# SulaMatikV2.net
KiCad netlist of a schematic drawn in EAGLE
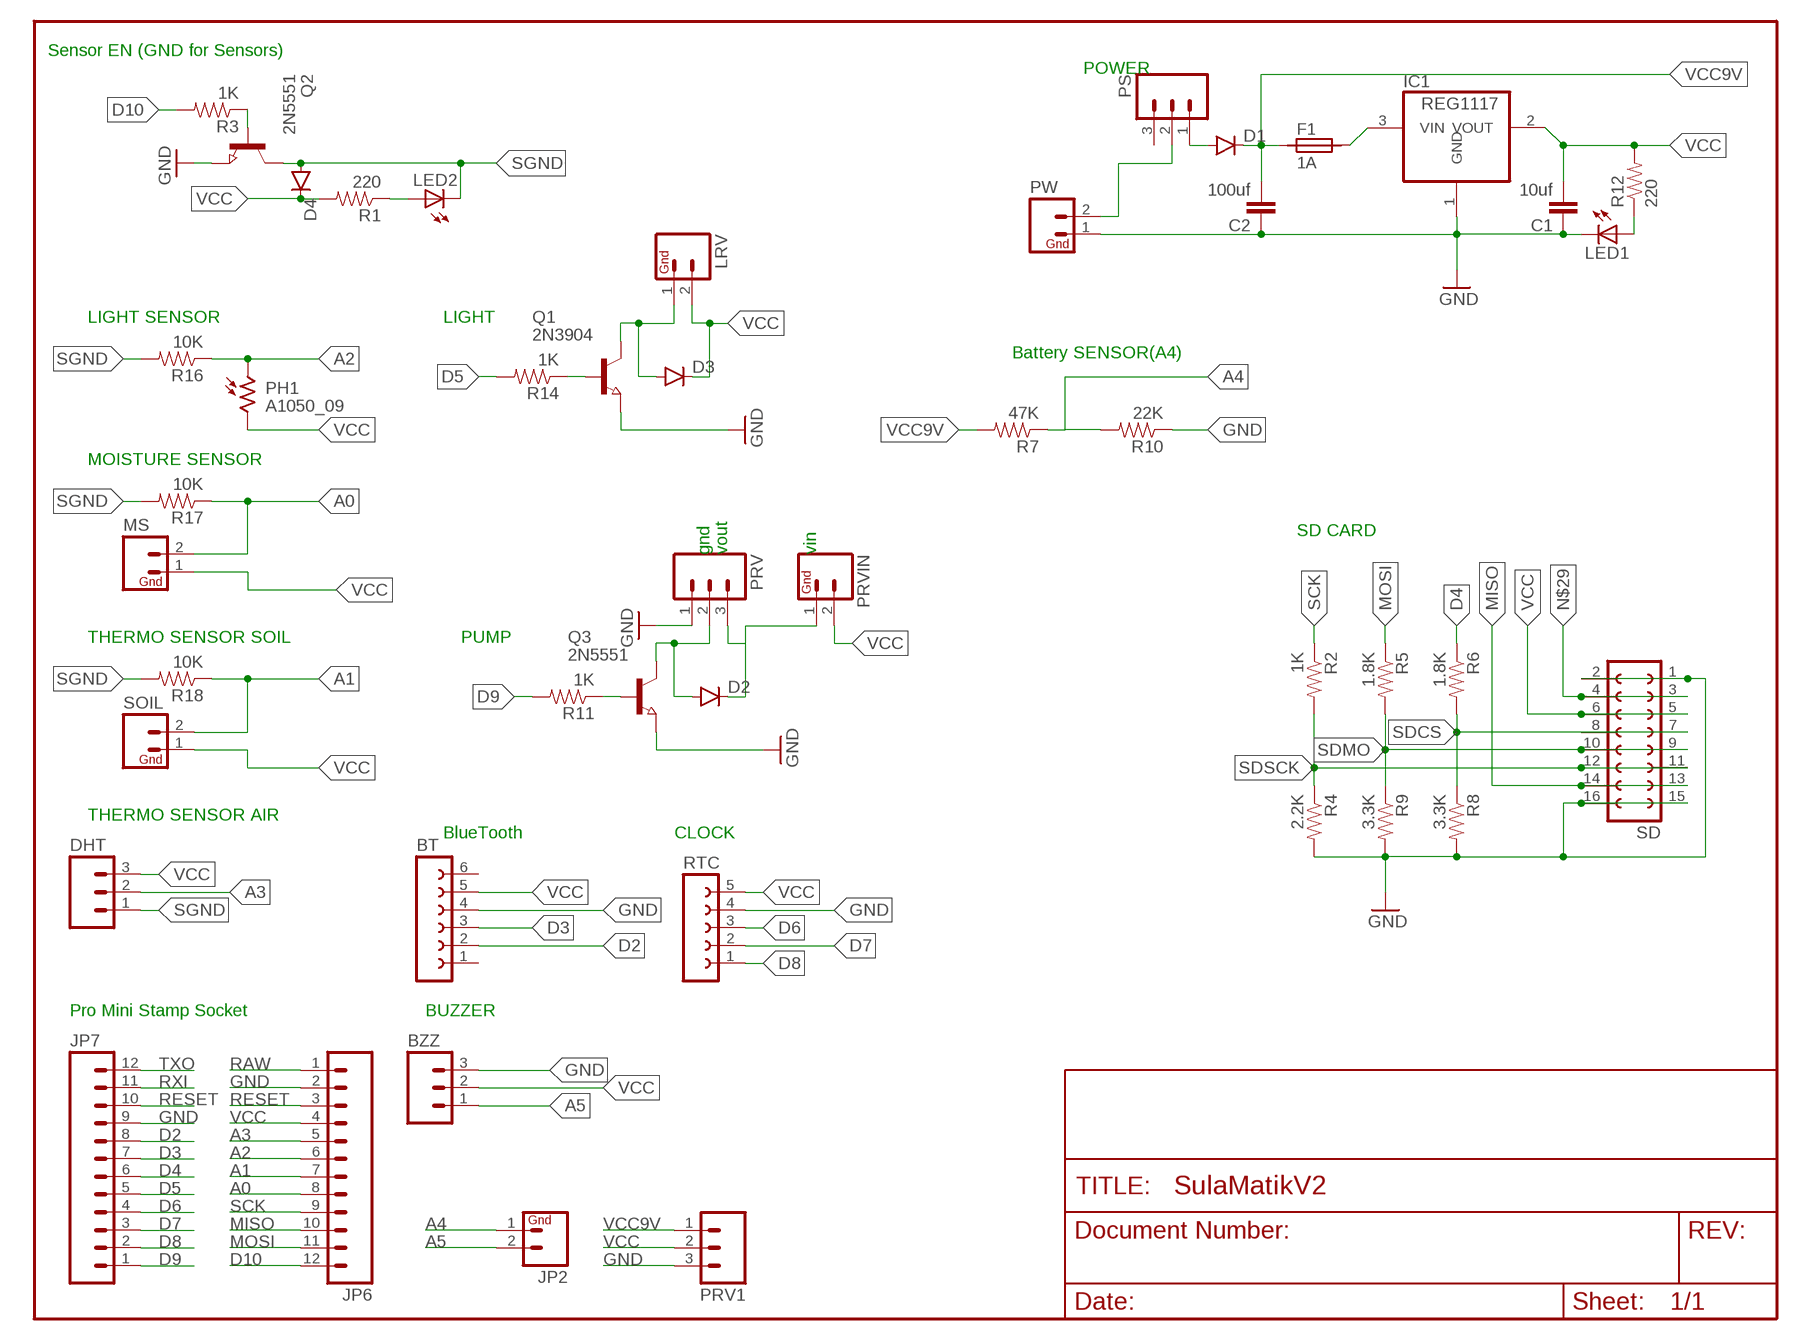
[diagram p0: schematic, sheet 1]

(export (version "E")
  (design (tool "Eeschema 10.0.6"))
  (components
    (comp (ref "BT")
      (value "FE06-1")
      (footprint "eagle-import:FE06")
      (libsource (lib "eagle-import") (part "FE06-1"))
    )
    (comp (ref "BZZ")
      (value "M03PTH")
      (footprint "eagle-import:1X03")
      (libsource (lib "eagle-import") (part "M03PTH"))
    )
    (comp (ref "C1")
      (value "10uf")
      (footprint "eagle-import:0805")
      (libsource (lib "eagle-import") (part "CAP0805"))
    )
    (comp (ref "C2")
      (value "100uf")
      (footprint "eagle-import:0805")
      (libsource (lib "eagle-import") (part "CAP0805"))
    )
    (comp (ref "D1")
      (value "DIODESMA")
      (footprint "eagle-import:SMA-DIODE")
      (libsource (lib "eagle-import") (part "DIODESMA"))
    )
    (comp (ref "D2")
      (value "DIODESMA")
      (footprint "eagle-import:SMA-DIODE")
      (libsource (lib "eagle-import") (part "DIODESMA"))
    )
    (comp (ref "D3")
      (value "DIODESMA")
      (footprint "eagle-import:SMA-DIODE")
      (libsource (lib "eagle-import") (part "DIODESMA"))
    )
    (comp (ref "D4")
      (value "DIODESMA")
      (footprint "eagle-import:SMA-DIODE")
      (libsource (lib "eagle-import") (part "DIODESMA"))
    )
    (comp (ref "DHT")
      (value "M03PTH")
      (footprint "eagle-import:1X03")
      (libsource (lib "eagle-import") (part "M03PTH"))
    )
    (comp (ref "F1")
      (value "1A")
      (footprint "eagle-import:1820")
      (libsource (lib "eagle-import") (part "SIBA194600"))
    )
    (comp (ref "IC1")
      (value "REG1117")
      (footprint "eagle-import:SOT223")
      (libsource (lib "eagle-import") (part "REG1117"))
    )
    (comp (ref "JP2")
      (value "M02PTH")
      (footprint "eagle-import:1X02")
      (libsource (lib "eagle-import") (part "M02PTH"))
    )
    (comp (ref "JP6")
      (value "M12PTH")
      (footprint "eagle-import:1X12")
      (libsource (lib "eagle-import") (part "M12PTH"))
    )
    (comp (ref "JP7")
      (value "M12PTH")
      (footprint "eagle-import:1X12")
      (libsource (lib "eagle-import") (part "M12PTH"))
    )
    (comp (ref "LED1")
      (value "LEDCHIP-LED0805")
      (footprint "eagle-import:CHIP-LED0805")
      (libsource (lib "eagle-import") (part "LEDCHIP-LED0805"))
    )
    (comp (ref "LED2")
      (value "LEDCHIP-LED0805")
      (footprint "eagle-import:CHIP-LED0805")
      (libsource (lib "eagle-import") (part "LEDCHIP-LED0805"))
    )
    (comp (ref "LRV")
      (value "M02PTH")
      (footprint "eagle-import:1X02")
      (libsource (lib "eagle-import") (part "M02PTH"))
    )
    (comp (ref "MS")
      (value "M02PTH")
      (footprint "eagle-import:1X02")
      (libsource (lib "eagle-import") (part "M02PTH"))
    )
    (comp (ref "PH1")
      (value "A1050_09")
      (footprint "eagle-import:T0-46-A10XX")
      (libsource (lib "eagle-import") (part "A1050_09"))
    )
    (comp (ref "PRV")
      (value "M03PTH")
      (footprint "eagle-import:1X03")
      (libsource (lib "eagle-import") (part "M03PTH"))
    )
    (comp (ref "PRV1")
      (value "M03PTH")
      (footprint "eagle-import:1X03")
      (libsource (lib "eagle-import") (part "M03PTH"))
    )
    (comp (ref "PRVIN")
      (value "M02PTH")
      (footprint "eagle-import:1X02")
      (libsource (lib "eagle-import") (part "M02PTH"))
    )
    (comp (ref "PS")
      (value "M03PTH")
      (footprint "eagle-import:1X03")
      (libsource (lib "eagle-import") (part "M03PTH"))
    )
    (comp (ref "PW")
      (value "M02PTH")
      (footprint "eagle-import:1X02")
      (libsource (lib "eagle-import") (part "M02PTH"))
    )
    (comp (ref "Q1")
      (value "2N3904")
      (footprint "eagle-import:SOT23")
      (libsource (lib "eagle-import") (part "NPN-TRANSISTOR_SOT23"))
    )
    (comp (ref "Q2")
      (value "2N5551")
      (footprint "eagle-import:SOT23")
      (libsource (lib "eagle-import") (part "NPN-TRANSISTOR_SOT23"))
    )
    (comp (ref "Q3")
      (value "2N5551")
      (footprint "eagle-import:SOT23")
      (libsource (lib "eagle-import") (part "NPN-TRANSISTOR_SOT23"))
    )
    (comp (ref "R1")
      (value "220")
      (footprint "eagle-import:0805")
      (libsource (lib "eagle-import") (part "RESISTOR0805-RES"))
    )
    (comp (ref "R2")
      (value "1K")
      (footprint "eagle-import:0805")
      (libsource (lib "eagle-import") (part "RESISTOR0805-RES"))
    )
    (comp (ref "R3")
      (value "1K")
      (footprint "eagle-import:0805")
      (libsource (lib "eagle-import") (part "RESISTOR0805-RES"))
    )
    (comp (ref "R4")
      (value "2.2K")
      (footprint "eagle-import:0805")
      (libsource (lib "eagle-import") (part "RESISTOR0805-RES"))
    )
    (comp (ref "R5")
      (value "1.8K")
      (footprint "eagle-import:0805")
      (libsource (lib "eagle-import") (part "RESISTOR0805-RES"))
    )
    (comp (ref "R6")
      (value "1.8K")
      (footprint "eagle-import:0805")
      (libsource (lib "eagle-import") (part "RESISTOR0805-RES"))
    )
    (comp (ref "R7")
      (value "47K")
      (footprint "eagle-import:0805")
      (libsource (lib "eagle-import") (part "RESISTOR0805-RES"))
    )
    (comp (ref "R8")
      (value "3.3K")
      (footprint "eagle-import:0805")
      (libsource (lib "eagle-import") (part "RESISTOR0805-RES"))
    )
    (comp (ref "R9")
      (value "3.3K")
      (footprint "eagle-import:0805")
      (libsource (lib "eagle-import") (part "RESISTOR0805-RES"))
    )
    (comp (ref "R10")
      (value "22K")
      (footprint "eagle-import:0805")
      (libsource (lib "eagle-import") (part "RESISTOR0805-RES"))
    )
    (comp (ref "R11")
      (value "1K")
      (footprint "eagle-import:0805")
      (libsource (lib "eagle-import") (part "RESISTOR0805-RES"))
    )
    (comp (ref "R12")
      (value "220")
      (footprint "eagle-import:0805")
      (libsource (lib "eagle-import") (part "RESISTOR0805-RES"))
    )
    (comp (ref "R14")
      (value "1K")
      (footprint "eagle-import:0805")
      (libsource (lib "eagle-import") (part "RESISTOR0805-RES"))
    )
    (comp (ref "R16")
      (value "10K")
      (footprint "eagle-import:0805")
      (libsource (lib "eagle-import") (part "RESISTOR0805-RES"))
    )
    (comp (ref "R17")
      (value "10K")
      (footprint "eagle-import:0805")
      (libsource (lib "eagle-import") (part "RESISTOR0805-RES"))
    )
    (comp (ref "R18")
      (value "10K")
      (footprint "eagle-import:0805")
      (libsource (lib "eagle-import") (part "RESISTOR0805-RES"))
    )
    (comp (ref "RTC")
      (value "FE05-1")
      (footprint "eagle-import:FE05-1")
      (libsource (lib "eagle-import") (part "FE05-1"))
    )
    (comp (ref "SD")
      (value "FE08-2")
      (footprint "eagle-import:FE08-2")
      (libsource (lib "eagle-import") (part "FE08-2"))
    )
    (comp (ref "SOIL")
      (value "M02PTH")
      (footprint "eagle-import:1X02")
      (libsource (lib "eagle-import") (part "M02PTH"))
    )
  )
  (nets
    (net (code "1") (name "/RAW") (class "Default")
      (node (ref "JP6") (pin "1") (pinfunction "1_1") (pintype "passive"))
    )
    (net (code "2") (name "/RESET") (class "Default")
      (node (ref "JP6") (pin "3") (pinfunction "3_3") (pintype "passive"))
      (node (ref "JP7") (pin "10") (pinfunction "10_10") (pintype "passive"))
    )
    (net (code "3") (name "/RXI") (class "Default")
      (node (ref "JP7") (pin "11") (pinfunction "11_11") (pintype "passive"))
    )
    (net (code "4") (name "/TXO") (class "Default")
      (node (ref "JP7") (pin "12") (pinfunction "12_12") (pintype "passive"))
    )
    (net (code "5") (name "A0") (class "Default")
      (node (ref "JP6") (pin "8") (pinfunction "8_8") (pintype "passive"))
      (node (ref "MS") (pin "2") (pinfunction "2_2") (pintype "passive"))
      (node (ref "R17") (pin "1") (pinfunction "1_1") (pintype "passive"))
    )
    (net (code "6") (name "A1") (class "Default")
      (node (ref "JP6") (pin "7") (pinfunction "7_7") (pintype "passive"))
      (node (ref "R18") (pin "1") (pinfunction "1_1") (pintype "passive"))
      (node (ref "SOIL") (pin "2") (pinfunction "2_2") (pintype "passive"))
    )
    (net (code "7") (name "A2") (class "Default")
      (node (ref "JP6") (pin "6") (pinfunction "6_6") (pintype "passive"))
      (node (ref "PH1") (pin "1") (pinfunction "1_1") (pintype "passive"))
      (node (ref "R16") (pin "1") (pinfunction "1_1") (pintype "passive"))
    )
    (net (code "8") (name "A3") (class "Default")
      (node (ref "DHT") (pin "2") (pinfunction "2_2") (pintype "passive"))
      (node (ref "JP6") (pin "5") (pinfunction "5_5") (pintype "passive"))
    )
    (net (code "9") (name "A4") (class "Default")
      (node (ref "JP2") (pin "1") (pinfunction "1_1") (pintype "passive"))
      (node (ref "R10") (pin "2") (pinfunction "2_2") (pintype "passive"))
      (node (ref "R7") (pin "1") (pinfunction "1_1") (pintype "passive"))
    )
    (net (code "10") (name "A5") (class "Default")
      (node (ref "BZZ") (pin "1") (pinfunction "1_1") (pintype "passive"))
      (node (ref "JP2") (pin "2") (pinfunction "2_2") (pintype "passive"))
    )
    (net (code "11") (name "D2") (class "Default")
      (node (ref "BT") (pin "2") (pinfunction "2_2") (pintype "passive"))
      (node (ref "JP7") (pin "8") (pinfunction "8_8") (pintype "passive"))
    )
    (net (code "12") (name "D3") (class "Default")
      (node (ref "BT") (pin "3") (pinfunction "3_3") (pintype "passive"))
      (node (ref "JP7") (pin "7") (pinfunction "7_7") (pintype "passive"))
    )
    (net (code "13") (name "D4") (class "Default")
      (node (ref "JP7") (pin "6") (pinfunction "6_6") (pintype "passive"))
      (node (ref "R6") (pin "1") (pinfunction "1_1") (pintype "passive"))
    )
    (net (code "14") (name "D5") (class "Default")
      (node (ref "JP7") (pin "5") (pinfunction "5_5") (pintype "passive"))
      (node (ref "R14") (pin "2") (pinfunction "2_2") (pintype "passive"))
    )
    (net (code "15") (name "D6") (class "Default")
      (node (ref "JP7") (pin "4") (pinfunction "4_4") (pintype "passive"))
      (node (ref "RTC") (pin "3") (pinfunction "3_3") (pintype "passive"))
    )
    (net (code "16") (name "D7") (class "Default")
      (node (ref "JP7") (pin "3") (pinfunction "3_3") (pintype "passive"))
      (node (ref "RTC") (pin "2") (pinfunction "2_2") (pintype "passive"))
    )
    (net (code "17") (name "D8") (class "Default")
      (node (ref "JP7") (pin "2") (pinfunction "2_2") (pintype "passive"))
      (node (ref "RTC") (pin "1") (pinfunction "1_1") (pintype "passive"))
    )
    (net (code "18") (name "D9") (class "Default")
      (node (ref "JP7") (pin "1") (pinfunction "1_1") (pintype "passive"))
      (node (ref "R11") (pin "2") (pinfunction "2_2") (pintype "passive"))
    )
    (net (code "19") (name "D10") (class "Default")
      (node (ref "JP6") (pin "12") (pinfunction "12_12") (pintype "passive"))
      (node (ref "R3") (pin "2") (pinfunction "2_2") (pintype "passive"))
    )
    (net (code "20") (name "GND") (class "Default")
      (node (ref "BT") (pin "4") (pinfunction "4_4") (pintype "passive"))
      (node (ref "BZZ") (pin "3") (pinfunction "3_3") (pintype "passive"))
      (node (ref "C1") (pin "1") (pinfunction "1_1") (pintype "passive"))
      (node (ref "C2") (pin "1") (pinfunction "1_1") (pintype "passive"))
      (node (ref "IC1") (pin "1") (pinfunction "GND_1") (pintype "power_in"))
      (node (ref "JP6") (pin "2") (pinfunction "2_2") (pintype "passive"))
      (node (ref "JP7") (pin "9") (pinfunction "9_9") (pintype "passive"))
      (node (ref "LED1") (pin "C") (pinfunction "C_C") (pintype "passive"))
      (node (ref "PRV") (pin "1") (pinfunction "1_1") (pintype "passive"))
      (node (ref "PRV1") (pin "3") (pinfunction "3_3") (pintype "passive"))
      (node (ref "PW") (pin "1") (pinfunction "1_1") (pintype "passive"))
      (node (ref "Q1") (pin "2") (pinfunction "E_2") (pintype "passive"))
      (node (ref "Q2") (pin "2") (pinfunction "E_2") (pintype "passive"))
      (node (ref "Q3") (pin "2") (pinfunction "E_2") (pintype "passive"))
      (node (ref "R10") (pin "1") (pinfunction "1_1") (pintype "passive"))
      (node (ref "R4") (pin "2") (pinfunction "2_2") (pintype "passive"))
      (node (ref "R8") (pin "2") (pinfunction "2_2") (pintype "passive"))
      (node (ref "R9") (pin "2") (pinfunction "2_2") (pintype "passive"))
      (node (ref "RTC") (pin "4") (pinfunction "4_4") (pintype "passive"))
      (node (ref "SD") (pin "1") (pinfunction "1_1") (pintype "passive"))
      (node (ref "SD") (pin "15") (pinfunction "15_15") (pintype "passive"))
      (node (ref "SD") (pin "16") (pinfunction "16_16") (pintype "passive"))
      (node (ref "SD") (pin "2") (pinfunction "2_2") (pintype "passive"))
    )
    (net (code "21") (name "MISO") (class "Default")
      (node (ref "JP6") (pin "10") (pinfunction "10_10") (pintype "passive"))
      (node (ref "SD") (pin "13") (pinfunction "13_13") (pintype "passive"))
      (node (ref "SD") (pin "14") (pinfunction "14_14") (pintype "passive"))
    )
    (net (code "22") (name "MOSI") (class "Default")
      (node (ref "JP6") (pin "11") (pinfunction "11_11") (pintype "passive"))
      (node (ref "R5") (pin "1") (pinfunction "1_1") (pintype "passive"))
    )
    (net (code "23") (name "N$29") (class "Default")
      (node (ref "SD") (pin "3") (pinfunction "3_3") (pintype "passive"))
      (node (ref "SD") (pin "4") (pinfunction "4_4") (pintype "passive"))
    )
    (net (code "24") (name "Net-(D1-PadA)") (class "Default")
      (node (ref "D1") (pin "A") (pinfunction "A_A") (pintype "passive"))
      (node (ref "PS") (pin "1") (pinfunction "1_1") (pintype "passive"))
    )
    (net (code "25") (name "Net-(D2-PadC)") (class "Default")
      (node (ref "D2") (pin "C") (pinfunction "C_C") (pintype "passive"))
      (node (ref "PRV") (pin "3") (pinfunction "3_3") (pintype "passive"))
      (node (ref "PRVIN") (pin "1") (pinfunction "1_1") (pintype "passive"))
    )
    (net (code "26") (name "Net-(IC1-VIN)") (class "Default")
      (node (ref "F1") (pin "2") (pinfunction "2_2") (pintype "passive"))
      (node (ref "IC1") (pin "3") (pinfunction "VIN_3") (pintype "input"))
    )
    (net (code "27") (name "Net-(LED1-PadA)") (class "Default")
      (node (ref "LED1") (pin "A") (pinfunction "A_A") (pintype "passive"))
      (node (ref "R12") (pin "1") (pinfunction "1_1") (pintype "passive"))
    )
    (net (code "28") (name "Net-(LED2-PadA)") (class "Default")
      (node (ref "LED2") (pin "A") (pinfunction "A_A") (pintype "passive"))
      (node (ref "R1") (pin "1") (pinfunction "1_1") (pintype "passive"))
    )
    (net (code "29") (name "Net-(PS-Pad2)") (class "Default")
      (node (ref "PS") (pin "2") (pinfunction "2_2") (pintype "passive"))
      (node (ref "PW") (pin "2") (pinfunction "2_2") (pintype "passive"))
    )
    (net (code "30") (name "Net-(Q1-B)") (class "Default")
      (node (ref "Q1") (pin "1") (pinfunction "B_1") (pintype "passive"))
      (node (ref "R14") (pin "1") (pinfunction "1_1") (pintype "passive"))
    )
    (net (code "31") (name "Net-(Q1-C)") (class "Default")
      (node (ref "D3") (pin "A") (pinfunction "A_A") (pintype "passive"))
      (node (ref "LRV") (pin "1") (pinfunction "1_1") (pintype "passive"))
      (node (ref "Q1") (pin "3") (pinfunction "C_3") (pintype "passive"))
    )
    (net (code "32") (name "Net-(Q2-B)") (class "Default")
      (node (ref "Q2") (pin "1") (pinfunction "B_1") (pintype "passive"))
      (node (ref "R3") (pin "1") (pinfunction "1_1") (pintype "passive"))
    )
    (net (code "33") (name "Net-(Q3-B)") (class "Default")
      (node (ref "Q3") (pin "1") (pinfunction "B_1") (pintype "passive"))
      (node (ref "R11") (pin "1") (pinfunction "1_1") (pintype "passive"))
    )
    (net (code "34") (name "Net-(Q3-C)") (class "Default")
      (node (ref "D2") (pin "A") (pinfunction "A_A") (pintype "passive"))
      (node (ref "PRV") (pin "2") (pinfunction "2_2") (pintype "passive"))
      (node (ref "Q3") (pin "3") (pinfunction "C_3") (pintype "passive"))
    )
    (net (code "35") (name "SCK") (class "Default")
      (node (ref "JP6") (pin "9") (pinfunction "9_9") (pintype "passive"))
      (node (ref "R2") (pin "1") (pinfunction "1_1") (pintype "passive"))
    )
    (net (code "36") (name "SDCS") (class "Default")
      (node (ref "R6") (pin "2") (pinfunction "2_2") (pintype "passive"))
      (node (ref "R8") (pin "1") (pinfunction "1_1") (pintype "passive"))
      (node (ref "SD") (pin "7") (pinfunction "7_7") (pintype "passive"))
      (node (ref "SD") (pin "8") (pinfunction "8_8") (pintype "passive"))
    )
    (net (code "37") (name "SDMO") (class "Default")
      (node (ref "R5") (pin "2") (pinfunction "2_2") (pintype "passive"))
      (node (ref "R9") (pin "1") (pinfunction "1_1") (pintype "passive"))
      (node (ref "SD") (pin "10") (pinfunction "10_10") (pintype "passive"))
      (node (ref "SD") (pin "9") (pinfunction "9_9") (pintype "passive"))
    )
    (net (code "38") (name "SDSCK") (class "Default")
      (node (ref "R2") (pin "2") (pinfunction "2_2") (pintype "passive"))
      (node (ref "R4") (pin "1") (pinfunction "1_1") (pintype "passive"))
      (node (ref "SD") (pin "11") (pinfunction "11_11") (pintype "passive"))
      (node (ref "SD") (pin "12") (pinfunction "12_12") (pintype "passive"))
    )
    (net (code "39") (name "SGND") (class "Default")
      (node (ref "D4") (pin "A") (pinfunction "A_A") (pintype "passive"))
      (node (ref "DHT") (pin "1") (pinfunction "1_1") (pintype "passive"))
      (node (ref "LED2") (pin "C") (pinfunction "C_C") (pintype "passive"))
      (node (ref "Q2") (pin "3") (pinfunction "C_3") (pintype "passive"))
      (node (ref "R16") (pin "2") (pinfunction "2_2") (pintype "passive"))
      (node (ref "R17") (pin "2") (pinfunction "2_2") (pintype "passive"))
      (node (ref "R18") (pin "2") (pinfunction "2_2") (pintype "passive"))
    )
    (net (code "40") (name "VCC") (class "Default")
      (node (ref "BT") (pin "5") (pinfunction "5_5") (pintype "passive"))
      (node (ref "BZZ") (pin "2") (pinfunction "2_2") (pintype "passive"))
      (node (ref "C1") (pin "2") (pinfunction "2_2") (pintype "passive"))
      (node (ref "D3") (pin "C") (pinfunction "C_C") (pintype "passive"))
      (node (ref "D4") (pin "C") (pinfunction "C_C") (pintype "passive"))
      (node (ref "DHT") (pin "3") (pinfunction "3_3") (pintype "passive"))
      (node (ref "IC1") (pin "2") (pinfunction "VOUT_2") (pintype "output"))
      (node (ref "JP6") (pin "4") (pinfunction "4_4") (pintype "passive"))
      (node (ref "LRV") (pin "2") (pinfunction "2_2") (pintype "passive"))
      (node (ref "MS") (pin "1") (pinfunction "1_1") (pintype "passive"))
      (node (ref "PH1") (pin "2") (pinfunction "2_2") (pintype "passive"))
      (node (ref "PRV1") (pin "2") (pinfunction "2_2") (pintype "passive"))
      (node (ref "PRVIN") (pin "2") (pinfunction "2_2") (pintype "passive"))
      (node (ref "R1") (pin "2") (pinfunction "2_2") (pintype "passive"))
      (node (ref "R12") (pin "2") (pinfunction "2_2") (pintype "passive"))
      (node (ref "RTC") (pin "5") (pinfunction "5_5") (pintype "passive"))
      (node (ref "SD") (pin "5") (pinfunction "5_5") (pintype "passive"))
      (node (ref "SD") (pin "6") (pinfunction "6_6") (pintype "passive"))
      (node (ref "SOIL") (pin "1") (pinfunction "1_1") (pintype "passive"))
    )
    (net (code "41") (name "VCC9V") (class "Default")
      (node (ref "C2") (pin "2") (pinfunction "2_2") (pintype "passive"))
      (node (ref "D1") (pin "C") (pinfunction "C_C") (pintype "passive"))
      (node (ref "F1") (pin "1") (pinfunction "1_1") (pintype "passive"))
      (node (ref "PRV1") (pin "1") (pinfunction "1_1") (pintype "passive"))
      (node (ref "R7") (pin "2") (pinfunction "2_2") (pintype "passive"))
    )
    (net (code "42") (name "unconnected-(BT-Pad1)") (class "Default")
      (node (ref "BT") (pin "1") (pinfunction "1_1") (pintype "passive"))
    )
    (net (code "43") (name "unconnected-(BT-Pad6)") (class "Default")
      (node (ref "BT") (pin "6") (pinfunction "6_6") (pintype "passive"))
    )
    (net (code "44") (name "unconnected-(PS-Pad3)") (class "Default")
      (node (ref "PS") (pin "3") (pinfunction "3_3") (pintype "passive"))
    )
  )
)
